# mini-joystick.net
KiCad netlist of a schematic drawn in EAGLE
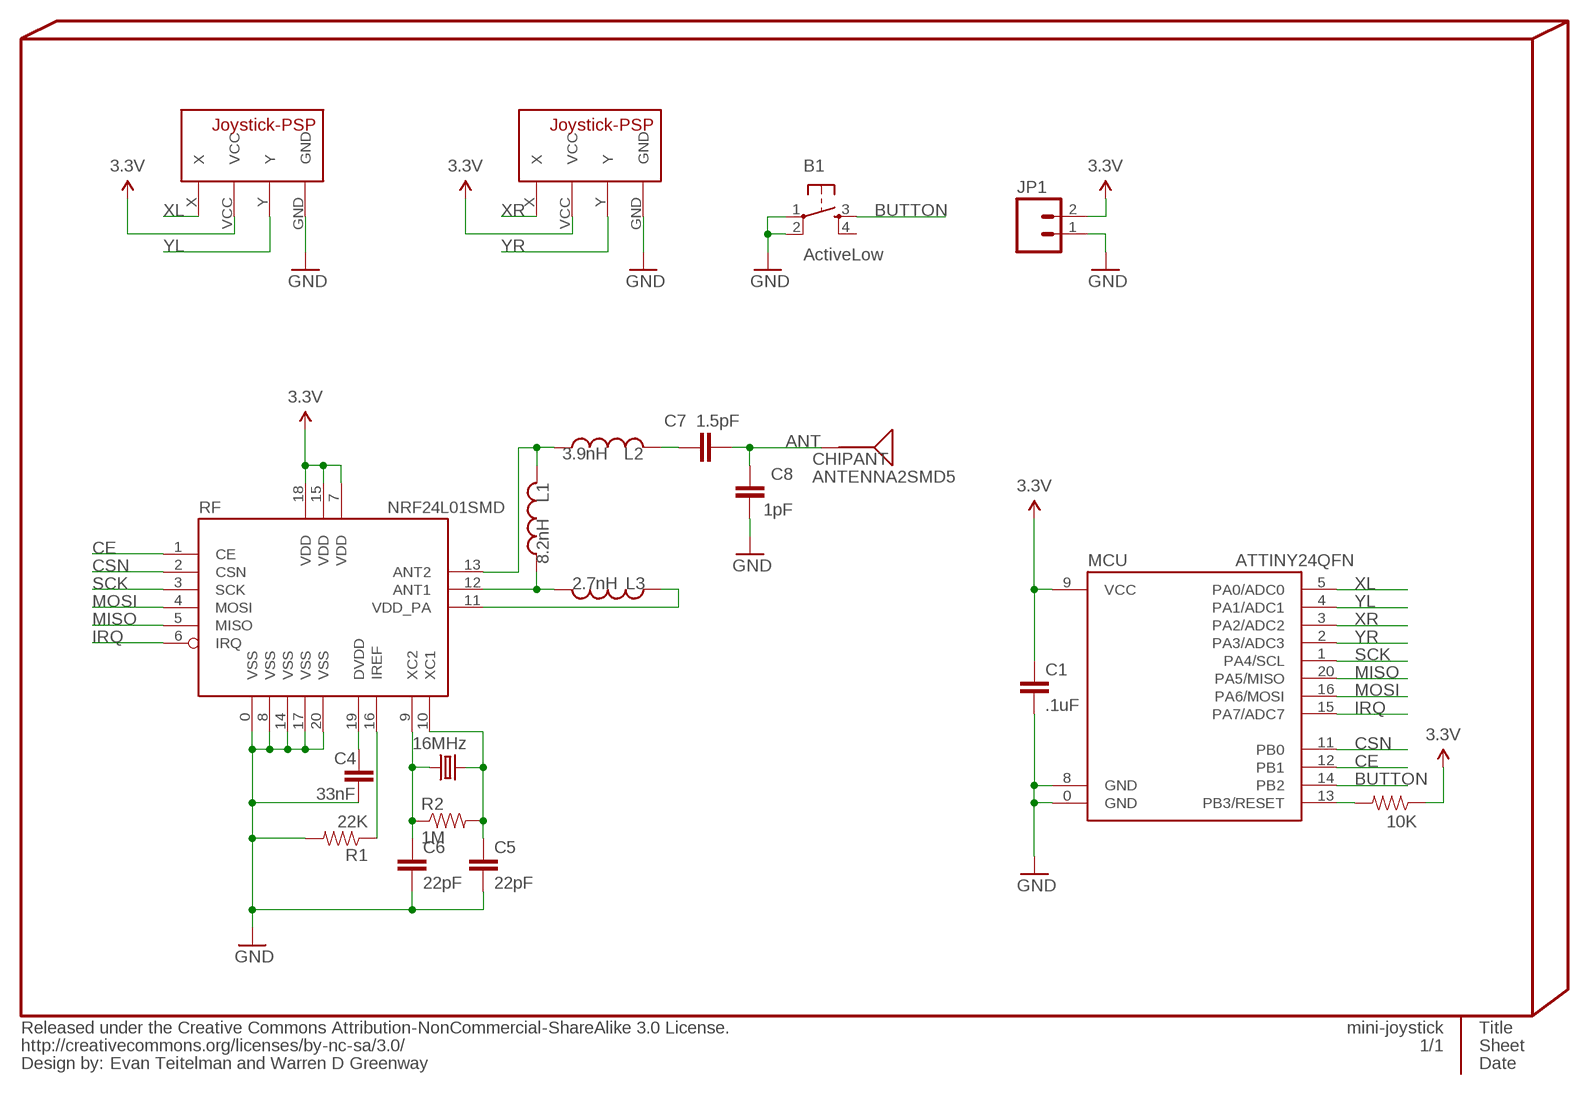
[diagram p0: schematic, sheet 1]

(export (version "E")
  (design (tool "Eeschema 10.0.6"))
  (components
    (comp (ref "B1")
      (value "ActiveLow")
      (footprint "eagle-import:TACTILE_SWITCH_SMD")
      (libsource (lib "eagle-import") (part "TAC_SWITCHSMD"))
    )
    (comp (ref "C1")
      (value ".1uF")
      (footprint "eagle-import:0402-CAP")
      (libsource (lib "eagle-import") (part "CAP0402-CAP"))
    )
    (comp (ref "C4")
      (value "33nF")
      (footprint "eagle-import:0402-CAP")
      (libsource (lib "eagle-import") (part "CAP0402-CAP"))
    )
    (comp (ref "C5")
      (value "22pF")
      (footprint "eagle-import:0402-CAP")
      (libsource (lib "eagle-import") (part "CAP0402-CAP"))
    )
    (comp (ref "C6")
      (value "22pF")
      (footprint "eagle-import:0402-CAP")
      (libsource (lib "eagle-import") (part "CAP0402-CAP"))
    )
    (comp (ref "C7")
      (value "1.5pF")
      (footprint "eagle-import:0402-CAP")
      (libsource (lib "eagle-import") (part "CAP0402-CAP"))
    )
    (comp (ref "C8")
      (value "1pF")
      (footprint "eagle-import:0402-CAP")
      (libsource (lib "eagle-import") (part "CAP0402-CAP"))
    )
    (comp (ref "CHIPANT")
      (value "ANTENNA2SMD5")
      (footprint "eagle-import:ANTENNA-CHIP5")
      (libsource (lib "eagle-import") (part "ANTENNA2SMD5"))
    )
    (comp (ref "INFO4")
      (value "Evan Teitelman and Warren D Greenway")
      (footprint "eagle-import:%CC-NC-SA")
      (libsource (lib "eagle-import") (part "%CC-NC-SA"))
    )
    (comp (ref "JOYSTICK_LEFT")
      (value "JOYSTICK-PSP1000NOHOLES")
      (footprint "eagle-import:JOYSTICK-PSP1000NH_")
      (libsource (lib "eagle-import") (part "JOYSTICK-PSP1000NOHOLES"))
    )
    (comp (ref "JOYSTICK_RIGHT")
      (value "JOYSTICK-PSP1000NOHOLES")
      (footprint "eagle-import:JOYSTICK-PSP1000NH_")
      (libsource (lib "eagle-import") (part "JOYSTICK-PSP1000NOHOLES"))
    )
    (comp (ref "JP1")
      (value "M02-JST-2MM-SMT")
      (footprint "eagle-import:JST-2-SMD")
      (libsource (lib "eagle-import") (part "M02-JST-2MM-SMT"))
    )
    (comp (ref "L1")
      (value "8.2nH")
      (footprint "eagle-import:C0402")
      (libsource (lib "eagle-import") (part "INDUCTOR0402"))
    )
    (comp (ref "L2")
      (value "3.9nH")
      (footprint "eagle-import:C0402")
      (libsource (lib "eagle-import") (part "INDUCTOR0402"))
    )
    (comp (ref "L3")
      (value "2.7nH")
      (footprint "eagle-import:C0402")
      (libsource (lib "eagle-import") (part "INDUCTOR0402"))
    )
    (comp (ref "MCU")
      (value "ATTINY24QFN")
      (footprint "eagle-import:QFN20")
      (libsource (lib "eagle-import") (part "ATTINY24QFN"))
    )
    (comp (ref "R1")
      (value "22K")
      (footprint "eagle-import:0603-RES")
      (libsource (lib "eagle-import") (part "RESISTOR0603-RES"))
    )
    (comp (ref "R2")
      (value "1M")
      (footprint "eagle-import:0603-RES")
      (libsource (lib "eagle-import") (part "RESISTOR0603-RES"))
    )
    (comp (ref "R3")
      (value "10K")
      (footprint "eagle-import:0402-RES")
      (libsource (lib "eagle-import") (part "RESISTOR0402-RES"))
    )
    (comp (ref "RF")
      (value "NRF24L01SMD")
      (footprint "eagle-import:QFN20")
      (libsource (lib "eagle-import") (part "NRF24L01SMD"))
    )
    (comp (ref "Y1")
      (value "16MHz")
      (footprint "eagle-import:CRYSTAL-SMD-5X3")
      (libsource (lib "eagle-import") (part "CRYSTAL5X3"))
    )
  )
  (nets
    (net (code "1") (name "/ANT") (class "Default")
      (node (ref "C7") (pin "2") (pinfunction "2_2") (pintype "passive"))
      (node (ref "C8") (pin "2") (pinfunction "2_2") (pintype "passive"))
      (node (ref "CHIPANT") (pin "FEED") (pinfunction "SIGNAL_FEED") (pintype "bidirectional"))
    )
    (net (code "2") (name "/BUTTON") (class "Default")
      (node (ref "B1") (pin "3") (pinfunction "3_3") (pintype "passive"))
      (node (ref "MCU") (pin "14") (pinfunction "PB2_14") (pintype "bidirectional"))
    )
    (net (code "3") (name "/CE") (class "Default")
      (node (ref "MCU") (pin "12") (pinfunction "PB1_12") (pintype "bidirectional"))
      (node (ref "RF") (pin "1") (pinfunction "CE_1") (pintype "input"))
    )
    (net (code "4") (name "/CSN") (class "Default")
      (node (ref "MCU") (pin "11") (pinfunction "PB0_11") (pintype "bidirectional"))
      (node (ref "RF") (pin "2") (pinfunction "CSN_2") (pintype "input"))
    )
    (net (code "5") (name "/IRQ") (class "Default")
      (node (ref "MCU") (pin "15") (pinfunction "PA7/ADC7_15") (pintype "bidirectional"))
      (node (ref "RF") (pin "6") (pinfunction "IRQ_6") (pintype "output"))
    )
    (net (code "6") (name "/MISO") (class "Default")
      (node (ref "MCU") (pin "20") (pinfunction "PA5/MISO_20") (pintype "bidirectional"))
      (node (ref "RF") (pin "5") (pinfunction "MISO_5") (pintype "output"))
    )
    (net (code "7") (name "/MOSI") (class "Default")
      (node (ref "MCU") (pin "16") (pinfunction "PA6/MOSI_16") (pintype "bidirectional"))
      (node (ref "RF") (pin "4") (pinfunction "MOSI_4") (pintype "input"))
    )
    (net (code "8") (name "/SCK") (class "Default")
      (node (ref "MCU") (pin "1") (pinfunction "PA4/SCL_1") (pintype "bidirectional"))
      (node (ref "RF") (pin "3") (pinfunction "SCK_3") (pintype "input"))
    )
    (net (code "9") (name "/XL") (class "Default")
      (node (ref "JOYSTICK_LEFT") (pin "X") (pinfunction "X_X") (pintype "bidirectional"))
      (node (ref "MCU") (pin "5") (pinfunction "PA0/ADC0_5") (pintype "bidirectional"))
    )
    (net (code "10") (name "/XR") (class "Default")
      (node (ref "JOYSTICK_RIGHT") (pin "X") (pinfunction "X_X") (pintype "bidirectional"))
      (node (ref "MCU") (pin "3") (pinfunction "PA2/ADC2_3") (pintype "bidirectional"))
    )
    (net (code "11") (name "/YL") (class "Default")
      (node (ref "JOYSTICK_LEFT") (pin "Y") (pinfunction "Y_Y") (pintype "bidirectional"))
      (node (ref "MCU") (pin "4") (pinfunction "PA1/ADC1_4") (pintype "bidirectional"))
    )
    (net (code "12") (name "/YR") (class "Default")
      (node (ref "JOYSTICK_RIGHT") (pin "Y") (pinfunction "Y_Y") (pintype "bidirectional"))
      (node (ref "MCU") (pin "2") (pinfunction "PA3/ADC3_2") (pintype "bidirectional"))
    )
    (net (code "13") (name "@3.3V") (class "Default")
      (node (ref "C1") (pin "1") (pinfunction "1_1") (pintype "passive"))
      (node (ref "JOYSTICK_LEFT") (pin "VCC") (pinfunction "VCC_VCC") (pintype "bidirectional"))
      (node (ref "JOYSTICK_RIGHT") (pin "VCC") (pinfunction "VCC_VCC") (pintype "bidirectional"))
      (node (ref "JP1") (pin "2") (pinfunction "2_2") (pintype "passive"))
      (node (ref "MCU") (pin "9") (pinfunction "VCC_9") (pintype "bidirectional"))
      (node (ref "R3") (pin "1") (pinfunction "1_1") (pintype "passive"))
      (node (ref "RF") (pin "15") (pinfunction "VDD_15") (pintype "power_in"))
      (node (ref "RF") (pin "18") (pinfunction "VDD_18") (pintype "power_in"))
      (node (ref "RF") (pin "7") (pinfunction "VDD_7") (pintype "power_in"))
    )
    (net (code "14") (name "@GND") (class "Default")
      (node (ref "B1") (pin "1") (pinfunction "1_1") (pintype "passive"))
      (node (ref "B1") (pin "2") (pinfunction "2_2") (pintype "passive"))
      (node (ref "C1") (pin "2") (pinfunction "2_2") (pintype "passive"))
      (node (ref "C4") (pin "2") (pinfunction "2_2") (pintype "passive"))
      (node (ref "C5") (pin "2") (pinfunction "2_2") (pintype "passive"))
      (node (ref "C6") (pin "2") (pinfunction "2_2") (pintype "passive"))
      (node (ref "C8") (pin "1") (pinfunction "1_1") (pintype "passive"))
      (node (ref "JOYSTICK_LEFT") (pin "GND") (pinfunction "GND_GND") (pintype "bidirectional"))
      (node (ref "JOYSTICK_RIGHT") (pin "GND") (pinfunction "GND_GND") (pintype "bidirectional"))
      (node (ref "JP1") (pin "1") (pinfunction "1_1") (pintype "passive"))
      (node (ref "MCU") (pin "0") (pinfunction "GND_0") (pintype "bidirectional"))
      (node (ref "MCU") (pin "8") (pinfunction "GND_8") (pintype "bidirectional"))
      (node (ref "R1") (pin "2") (pinfunction "2_2") (pintype "passive"))
      (node (ref "RF") (pin "0") (pinfunction "VSS_0") (pintype "power_in"))
      (node (ref "RF") (pin "14") (pinfunction "VSS_14") (pintype "power_in"))
      (node (ref "RF") (pin "17") (pinfunction "VSS_17") (pintype "power_in"))
      (node (ref "RF") (pin "20") (pinfunction "VSS_20") (pintype "power_in"))
      (node (ref "RF") (pin "8") (pinfunction "VSS_8") (pintype "power_in"))
    )
    (net (code "15") (name "Net-(C7-Pad1)") (class "Default")
      (node (ref "C7") (pin "1") (pinfunction "1_1") (pintype "passive"))
      (node (ref "L2") (pin "2") (pinfunction "2_2") (pintype "passive"))
    )
    (net (code "16") (name "Net-(MCU-PB3{slash}RESET)") (class "Default")
      (node (ref "MCU") (pin "13") (pinfunction "PB3/RESET_13") (pintype "bidirectional"))
      (node (ref "R3") (pin "2") (pinfunction "2_2") (pintype "passive"))
    )
    (net (code "17") (name "Net-(RF-ANT1)") (class "Default")
      (node (ref "L1") (pin "1") (pinfunction "1_1") (pintype "passive"))
      (node (ref "L3") (pin "2") (pinfunction "2_2") (pintype "passive"))
      (node (ref "RF") (pin "12") (pinfunction "ANT1_12") (pintype "output"))
    )
    (net (code "18") (name "Net-(RF-ANT2)") (class "Default")
      (node (ref "L1") (pin "2") (pinfunction "2_2") (pintype "passive"))
      (node (ref "L2") (pin "1") (pinfunction "1_1") (pintype "passive"))
      (node (ref "RF") (pin "13") (pinfunction "ANT2_13") (pintype "output"))
    )
    (net (code "19") (name "Net-(RF-DVDD)") (class "Default")
      (node (ref "C4") (pin "1") (pinfunction "1_1") (pintype "passive"))
      (node (ref "RF") (pin "19") (pinfunction "DVDD_19") (pintype "power_in"))
    )
    (net (code "20") (name "Net-(RF-IREF)") (class "Default")
      (node (ref "R1") (pin "1") (pinfunction "1_1") (pintype "passive"))
      (node (ref "RF") (pin "16") (pinfunction "IREF_16") (pintype "input"))
    )
    (net (code "21") (name "Net-(RF-VDD_PA)") (class "Default")
      (node (ref "L3") (pin "1") (pinfunction "1_1") (pintype "passive"))
      (node (ref "RF") (pin "11") (pinfunction "VDD_PA_11") (pintype "power_in"))
    )
    (net (code "22") (name "Net-(RF-XC1)") (class "Default")
      (node (ref "C5") (pin "1") (pinfunction "1_1") (pintype "passive"))
      (node (ref "R2") (pin "2") (pinfunction "2_2") (pintype "passive"))
      (node (ref "RF") (pin "10") (pinfunction "XC1_10") (pintype "input"))
      (node (ref "Y1") (pin "3") (pinfunction "2_3") (pintype "passive"))
    )
    (net (code "23") (name "Net-(RF-XC2)") (class "Default")
      (node (ref "C6") (pin "1") (pinfunction "1_1") (pintype "passive"))
      (node (ref "R2") (pin "1") (pinfunction "1_1") (pintype "passive"))
      (node (ref "RF") (pin "9") (pinfunction "XC2_9") (pintype "input"))
      (node (ref "Y1") (pin "1") (pinfunction "1_1") (pintype "passive"))
    )
    (net (code "24") (name "unconnected-(B1-Pad4)") (class "Default")
      (node (ref "B1") (pin "4") (pinfunction "4_4") (pintype "passive"))
    )
  )
)
